# switch.net
KiCad netlist of a schematic drawn in EAGLE
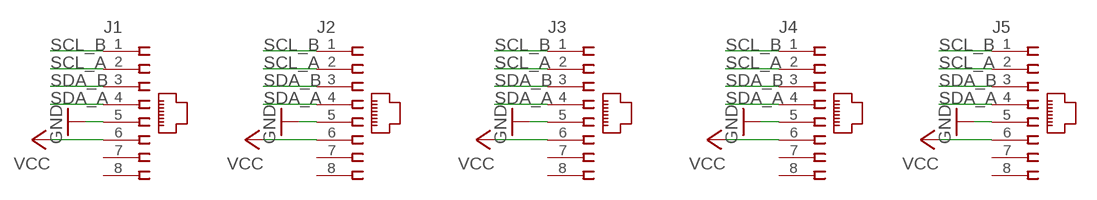
[diagram p0: schematic, sheet 1]

(export (version "E")
  (design (tool "Eeschema 10.0.6"))
  (components
    (comp (ref "J1")
      (value "215877-4")
      (footprint "eagle-import:215877-4")
      (libsource (lib "eagle-import") (part "215877-4"))
    )
    (comp (ref "J2")
      (value "215877-4")
      (footprint "eagle-import:215877-4")
      (libsource (lib "eagle-import") (part "215877-4"))
    )
    (comp (ref "J3")
      (value "215877-4")
      (footprint "eagle-import:215877-4")
      (libsource (lib "eagle-import") (part "215877-4"))
    )
    (comp (ref "J4")
      (value "215877-4")
      (footprint "eagle-import:215877-4")
      (libsource (lib "eagle-import") (part "215877-4"))
    )
    (comp (ref "J5")
      (value "215877-4")
      (footprint "eagle-import:215877-4")
      (libsource (lib "eagle-import") (part "215877-4"))
    )
  )
  (nets
    (net (code "1") (name "GND") (class "Default")
      (node (ref "J1") (pin "5") (pinfunction "5_5") (pintype "passive"))
      (node (ref "J2") (pin "5") (pinfunction "5_5") (pintype "passive"))
      (node (ref "J3") (pin "5") (pinfunction "5_5") (pintype "passive"))
      (node (ref "J4") (pin "5") (pinfunction "5_5") (pintype "passive"))
      (node (ref "J5") (pin "5") (pinfunction "5_5") (pintype "passive"))
    )
    (net (code "2") (name "SCL_A") (class "Default")
      (node (ref "J1") (pin "2") (pinfunction "2_2") (pintype "passive"))
      (node (ref "J2") (pin "2") (pinfunction "2_2") (pintype "passive"))
      (node (ref "J3") (pin "2") (pinfunction "2_2") (pintype "passive"))
      (node (ref "J4") (pin "2") (pinfunction "2_2") (pintype "passive"))
      (node (ref "J5") (pin "2") (pinfunction "2_2") (pintype "passive"))
    )
    (net (code "3") (name "SCL_B") (class "Default")
      (node (ref "J1") (pin "1") (pinfunction "1_1") (pintype "passive"))
      (node (ref "J2") (pin "1") (pinfunction "1_1") (pintype "passive"))
      (node (ref "J3") (pin "1") (pinfunction "1_1") (pintype "passive"))
      (node (ref "J4") (pin "1") (pinfunction "1_1") (pintype "passive"))
      (node (ref "J5") (pin "1") (pinfunction "1_1") (pintype "passive"))
    )
    (net (code "4") (name "SDA_A") (class "Default")
      (node (ref "J1") (pin "4") (pinfunction "4_4") (pintype "passive"))
      (node (ref "J2") (pin "4") (pinfunction "4_4") (pintype "passive"))
      (node (ref "J3") (pin "4") (pinfunction "4_4") (pintype "passive"))
      (node (ref "J4") (pin "4") (pinfunction "4_4") (pintype "passive"))
      (node (ref "J5") (pin "4") (pinfunction "4_4") (pintype "passive"))
    )
    (net (code "5") (name "SDA_B") (class "Default")
      (node (ref "J1") (pin "3") (pinfunction "3_3") (pintype "passive"))
      (node (ref "J2") (pin "3") (pinfunction "3_3") (pintype "passive"))
      (node (ref "J3") (pin "3") (pinfunction "3_3") (pintype "passive"))
      (node (ref "J4") (pin "3") (pinfunction "3_3") (pintype "passive"))
      (node (ref "J5") (pin "3") (pinfunction "3_3") (pintype "passive"))
    )
    (net (code "6") (name "VCC") (class "Default")
      (node (ref "J1") (pin "6") (pinfunction "6_6") (pintype "passive"))
      (node (ref "J2") (pin "6") (pinfunction "6_6") (pintype "passive"))
      (node (ref "J3") (pin "6") (pinfunction "6_6") (pintype "passive"))
      (node (ref "J4") (pin "6") (pinfunction "6_6") (pintype "passive"))
      (node (ref "J5") (pin "6") (pinfunction "6_6") (pintype "passive"))
    )
    (net (code "7") (name "unconnected-(J1-Pad7)") (class "Default")
      (node (ref "J1") (pin "7") (pinfunction "7_7") (pintype "passive"))
    )
    (net (code "8") (name "unconnected-(J1-Pad8)") (class "Default")
      (node (ref "J1") (pin "8") (pinfunction "8_8") (pintype "passive"))
    )
    (net (code "9") (name "unconnected-(J2-Pad7)") (class "Default")
      (node (ref "J2") (pin "7") (pinfunction "7_7") (pintype "passive"))
    )
    (net (code "10") (name "unconnected-(J2-Pad8)") (class "Default")
      (node (ref "J2") (pin "8") (pinfunction "8_8") (pintype "passive"))
    )
    (net (code "11") (name "unconnected-(J3-Pad7)") (class "Default")
      (node (ref "J3") (pin "7") (pinfunction "7_7") (pintype "passive"))
    )
    (net (code "12") (name "unconnected-(J3-Pad8)") (class "Default")
      (node (ref "J3") (pin "8") (pinfunction "8_8") (pintype "passive"))
    )
    (net (code "13") (name "unconnected-(J4-Pad7)") (class "Default")
      (node (ref "J4") (pin "7") (pinfunction "7_7") (pintype "passive"))
    )
    (net (code "14") (name "unconnected-(J4-Pad8)") (class "Default")
      (node (ref "J4") (pin "8") (pinfunction "8_8") (pintype "passive"))
    )
    (net (code "15") (name "unconnected-(J5-Pad7)") (class "Default")
      (node (ref "J5") (pin "7") (pinfunction "7_7") (pintype "passive"))
    )
    (net (code "16") (name "unconnected-(J5-Pad8)") (class "Default")
      (node (ref "J5") (pin "8") (pinfunction "8_8") (pintype "passive"))
    )
  )
)
